# untitled.net
KiCad netlist of a schematic drawn in EAGLE
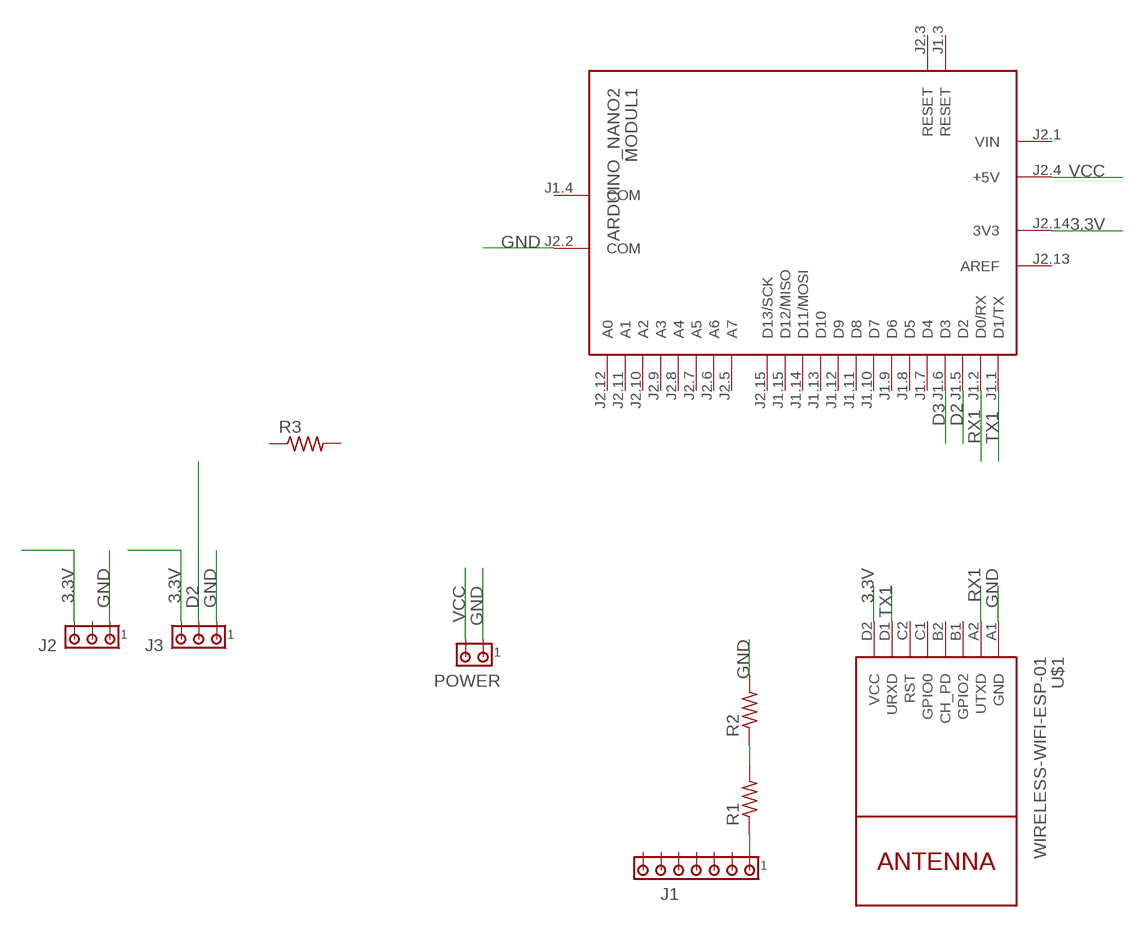
[diagram p0: schematic, sheet 1]

(export (version "E")
  (design (tool "Eeschema 10.0.6"))
  (components
    (comp (ref "J1")
      (value "MTA07-100")
      (footprint "eagle-import:10X07MTA")
      (libsource (lib "eagle-import") (part "MTA07-100"))
    )
    (comp (ref "J2")
      (value "MTA03-100")
      (footprint "eagle-import:10X03MTA")
      (libsource (lib "eagle-import") (part "MTA03-100"))
    )
    (comp (ref "J3")
      (value "MTA03-100")
      (footprint "eagle-import:10X03MTA")
      (libsource (lib "eagle-import") (part "MTA03-100"))
    )
    (comp (ref "MODUL1")
      (value "ARDUINO_NANO2")
      (footprint "eagle-import:ARDUINO_NANO2")
      (libsource (lib "eagle-import") (part "ARDUINO_NANO2"))
    )
    (comp (ref "POWER")
      (value "MTA02-100")
      (footprint "eagle-import:10X02MTA")
      (libsource (lib "eagle-import") (part "MTA02-100"))
    )
    (comp (ref "R1")
      (value "R-US_0207/9")
      (footprint "eagle-import:0207_9")
      (libsource (lib "eagle-import") (part "R-US_0207/9"))
    )
    (comp (ref "R2")
      (value "R-US_0207/9")
      (footprint "eagle-import:0207_9")
      (libsource (lib "eagle-import") (part "R-US_0207/9"))
    )
    (comp (ref "R3")
      (value "R-US_0207/9")
      (footprint "eagle-import:0207_9")
      (libsource (lib "eagle-import") (part "R-US_0207/9"))
    )
    (comp (ref "U$1")
      (value "WIRELESS-WIFI-ESP-01")
      (footprint "eagle-import:WIRELESS-WIFI-ESP-01")
      (libsource (lib "eagle-import") (part "WIRELESS-WIFI-ESP-01"))
    )
  )
  (nets
    (net (code "1") (name "/3.3V") (class "Default")
      (node (ref "J2") (pin "3") (pinfunction "3_3") (pintype "passive"))
      (node (ref "J3") (pin "3") (pinfunction "3_3") (pintype "passive"))
      (node (ref "MODUL1") (pin "J2.14") (pinfunction "3V3_J2.14") (pintype "power_in"))
      (node (ref "U$1") (pin "D2") (pinfunction "VCC_D2") (pintype "power_in"))
    )
    (net (code "2") (name "/AREF") (class "Default")
      (node (ref "MODUL1") (pin "J2.13") (pinfunction "AREF_J2.13") (pintype "power_in"))
    )
    (net (code "3") (name "/COM") (class "Default")
      (node (ref "MODUL1") (pin "J1.4") (pinfunction "COM_J1.4") (pintype "power_in"))
    )
    (net (code "4") (name "/D2") (class "Default")
      (node (ref "J3") (pin "2") (pinfunction "2_2") (pintype "passive"))
      (node (ref "MODUL1") (pin "J1.5") (pinfunction "D2_J1.5") (pintype "bidirectional"))
    )
    (net (code "5") (name "/D3") (class "Default")
      (node (ref "MODUL1") (pin "J1.6") (pinfunction "D3_J1.6") (pintype "bidirectional"))
    )
    (net (code "6") (name "/GND") (class "Default")
      (node (ref "J2") (pin "1") (pinfunction "1_1") (pintype "passive"))
      (node (ref "J3") (pin "1") (pinfunction "1_1") (pintype "passive"))
      (node (ref "MODUL1") (pin "J2.2") (pinfunction "COM_J2.2") (pintype "power_in"))
      (node (ref "POWER") (pin "1") (pinfunction "1_1") (pintype "passive"))
      (node (ref "R2") (pin "2") (pinfunction "2_2") (pintype "passive"))
      (node (ref "U$1") (pin "A1") (pinfunction "GND_A1") (pintype "power_in"))
    )
    (net (code "7") (name "/RX1") (class "Default")
      (node (ref "MODUL1") (pin "J1.2") (pinfunction "D0/RX_J1.2") (pintype "bidirectional"))
      (node (ref "U$1") (pin "A2") (pinfunction "UTXD_A2") (pintype "bidirectional"))
    )
    (net (code "8") (name "/TX1") (class "Default")
      (node (ref "MODUL1") (pin "J1.1") (pinfunction "D1/TX_J1.1") (pintype "bidirectional"))
      (node (ref "U$1") (pin "D1") (pinfunction "URXD_D1") (pintype "bidirectional"))
    )
    (net (code "9") (name "/VCC") (class "Default")
      (node (ref "MODUL1") (pin "J2.4") (pinfunction "+5V_J2.4") (pintype "power_in"))
      (node (ref "POWER") (pin "2") (pinfunction "2_2") (pintype "passive"))
    )
    (net (code "10") (name "/VIN") (class "Default")
      (node (ref "MODUL1") (pin "J2.1") (pinfunction "VIN_J2.1") (pintype "power_in"))
    )
    (net (code "11") (name "Net-(J1-Pad1)") (class "Default")
      (node (ref "J1") (pin "1") (pinfunction "1_1") (pintype "passive"))
      (node (ref "R1") (pin "1") (pinfunction "1_1") (pintype "passive"))
    )
    (net (code "12") (name "Net-(R1-Pad2)") (class "Default")
      (node (ref "R1") (pin "2") (pinfunction "2_2") (pintype "passive"))
      (node (ref "R2") (pin "1") (pinfunction "1_1") (pintype "passive"))
    )
    (net (code "13") (name "unconnected-(J1-Pad2)") (class "Default")
      (node (ref "J1") (pin "2") (pinfunction "2_2") (pintype "passive"))
    )
    (net (code "14") (name "unconnected-(J1-Pad3)") (class "Default")
      (node (ref "J1") (pin "3") (pinfunction "3_3") (pintype "passive"))
    )
    (net (code "15") (name "unconnected-(J1-Pad4)") (class "Default")
      (node (ref "J1") (pin "4") (pinfunction "4_4") (pintype "passive"))
    )
    (net (code "16") (name "unconnected-(J1-Pad5)") (class "Default")
      (node (ref "J1") (pin "5") (pinfunction "5_5") (pintype "passive"))
    )
    (net (code "17") (name "unconnected-(J1-Pad6)") (class "Default")
      (node (ref "J1") (pin "6") (pinfunction "6_6") (pintype "passive"))
    )
    (net (code "18") (name "unconnected-(J1-Pad7)") (class "Default")
      (node (ref "J1") (pin "7") (pinfunction "7_7") (pintype "passive"))
    )
    (net (code "19") (name "unconnected-(J2-Pad2)") (class "Default")
      (node (ref "J2") (pin "2") (pinfunction "2_2") (pintype "passive"))
    )
    (net (code "20") (name "unconnected-(MODUL1-A0-PadJ2.12)") (class "Default")
      (node (ref "MODUL1") (pin "J2.12") (pinfunction "A0_J2.12") (pintype "bidirectional"))
    )
    (net (code "21") (name "unconnected-(MODUL1-A1-PadJ2.11)") (class "Default")
      (node (ref "MODUL1") (pin "J2.11") (pinfunction "A1_J2.11") (pintype "bidirectional"))
    )
    (net (code "22") (name "unconnected-(MODUL1-A2-PadJ2.10)") (class "Default")
      (node (ref "MODUL1") (pin "J2.10") (pinfunction "A2_J2.10") (pintype "bidirectional"))
    )
    (net (code "23") (name "unconnected-(MODUL1-A3-PadJ2.9)") (class "Default")
      (node (ref "MODUL1") (pin "J2.9") (pinfunction "A3_J2.9") (pintype "bidirectional"))
    )
    (net (code "24") (name "unconnected-(MODUL1-A4-PadJ2.8)") (class "Default")
      (node (ref "MODUL1") (pin "J2.8") (pinfunction "A4_J2.8") (pintype "bidirectional"))
    )
    (net (code "25") (name "unconnected-(MODUL1-A5-PadJ2.7)") (class "Default")
      (node (ref "MODUL1") (pin "J2.7") (pinfunction "A5_J2.7") (pintype "bidirectional"))
    )
    (net (code "26") (name "unconnected-(MODUL1-A6-PadJ2.6)") (class "Default")
      (node (ref "MODUL1") (pin "J2.6") (pinfunction "A6_J2.6") (pintype "bidirectional"))
    )
    (net (code "27") (name "unconnected-(MODUL1-A7-PadJ2.5)") (class "Default")
      (node (ref "MODUL1") (pin "J2.5") (pinfunction "A7_J2.5") (pintype "bidirectional"))
    )
    (net (code "28") (name "unconnected-(MODUL1-D4-PadJ1.7)") (class "Default")
      (node (ref "MODUL1") (pin "J1.7") (pinfunction "D4_J1.7") (pintype "bidirectional"))
    )
    (net (code "29") (name "unconnected-(MODUL1-D5-PadJ1.8)") (class "Default")
      (node (ref "MODUL1") (pin "J1.8") (pinfunction "D5_J1.8") (pintype "bidirectional"))
    )
    (net (code "30") (name "unconnected-(MODUL1-D6-PadJ1.9)") (class "Default")
      (node (ref "MODUL1") (pin "J1.9") (pinfunction "D6_J1.9") (pintype "bidirectional"))
    )
    (net (code "31") (name "unconnected-(MODUL1-D7-PadJ1.10)") (class "Default")
      (node (ref "MODUL1") (pin "J1.10") (pinfunction "D7_J1.10") (pintype "bidirectional"))
    )
    (net (code "32") (name "unconnected-(MODUL1-D8-PadJ1.11)") (class "Default")
      (node (ref "MODUL1") (pin "J1.11") (pinfunction "D8_J1.11") (pintype "bidirectional"))
    )
    (net (code "33") (name "unconnected-(MODUL1-D9-PadJ1.12)") (class "Default")
      (node (ref "MODUL1") (pin "J1.12") (pinfunction "D9_J1.12") (pintype "bidirectional"))
    )
    (net (code "34") (name "unconnected-(MODUL1-D10-PadJ1.13)") (class "Default")
      (node (ref "MODUL1") (pin "J1.13") (pinfunction "D10_J1.13") (pintype "bidirectional"))
    )
    (net (code "35") (name "unconnected-(MODUL1-D11{slash}MOSI-PadJ1.14)") (class "Default")
      (node (ref "MODUL1") (pin "J1.14") (pinfunction "D11/MOSI_J1.14") (pintype "bidirectional"))
    )
    (net (code "36") (name "unconnected-(MODUL1-D12{slash}MISO-PadJ1.15)") (class "Default")
      (node (ref "MODUL1") (pin "J1.15") (pinfunction "D12/MISO_J1.15") (pintype "bidirectional"))
    )
    (net (code "37") (name "unconnected-(MODUL1-D13{slash}SCK-PadJ2.15)") (class "Default")
      (node (ref "MODUL1") (pin "J2.15") (pinfunction "D13/SCK_J2.15") (pintype "bidirectional"))
    )
    (net (code "38") (name "unconnected-(MODUL1-RESET-PadJ1.3)") (class "Default")
      (node (ref "MODUL1") (pin "J1.3") (pinfunction "RESET_J1.3") (pintype "bidirectional"))
    )
    (net (code "39") (name "unconnected-(MODUL1-RESET-PadJ2.3)") (class "Default")
      (node (ref "MODUL1") (pin "J2.3") (pinfunction "RESET_J2.3") (pintype "bidirectional"))
    )
    (net (code "40") (name "unconnected-(R3-Pad1)") (class "Default")
      (node (ref "R3") (pin "1") (pinfunction "1_1") (pintype "passive"))
    )
    (net (code "41") (name "unconnected-(R3-Pad2)") (class "Default")
      (node (ref "R3") (pin "2") (pinfunction "2_2") (pintype "passive"))
    )
    (net (code "42") (name "unconnected-(U$1-CH_PD-PadB2)") (class "Default")
      (node (ref "U$1") (pin "B2") (pinfunction "CH_PD_B2") (pintype "bidirectional"))
    )
    (net (code "43") (name "unconnected-(U$1-GPIO0-PadC1)") (class "Default")
      (node (ref "U$1") (pin "C1") (pinfunction "GPIO0_C1") (pintype "bidirectional"))
    )
    (net (code "44") (name "unconnected-(U$1-GPIO2-PadB1)") (class "Default")
      (node (ref "U$1") (pin "B1") (pinfunction "GPIO2_B1") (pintype "bidirectional"))
    )
    (net (code "45") (name "unconnected-(U$1-RST-PadC2)") (class "Default")
      (node (ref "U$1") (pin "C2") (pinfunction "RST_C2") (pintype "bidirectional"))
    )
  )
)
